# receiver.net
KiCad netlist of a schematic drawn in EAGLE
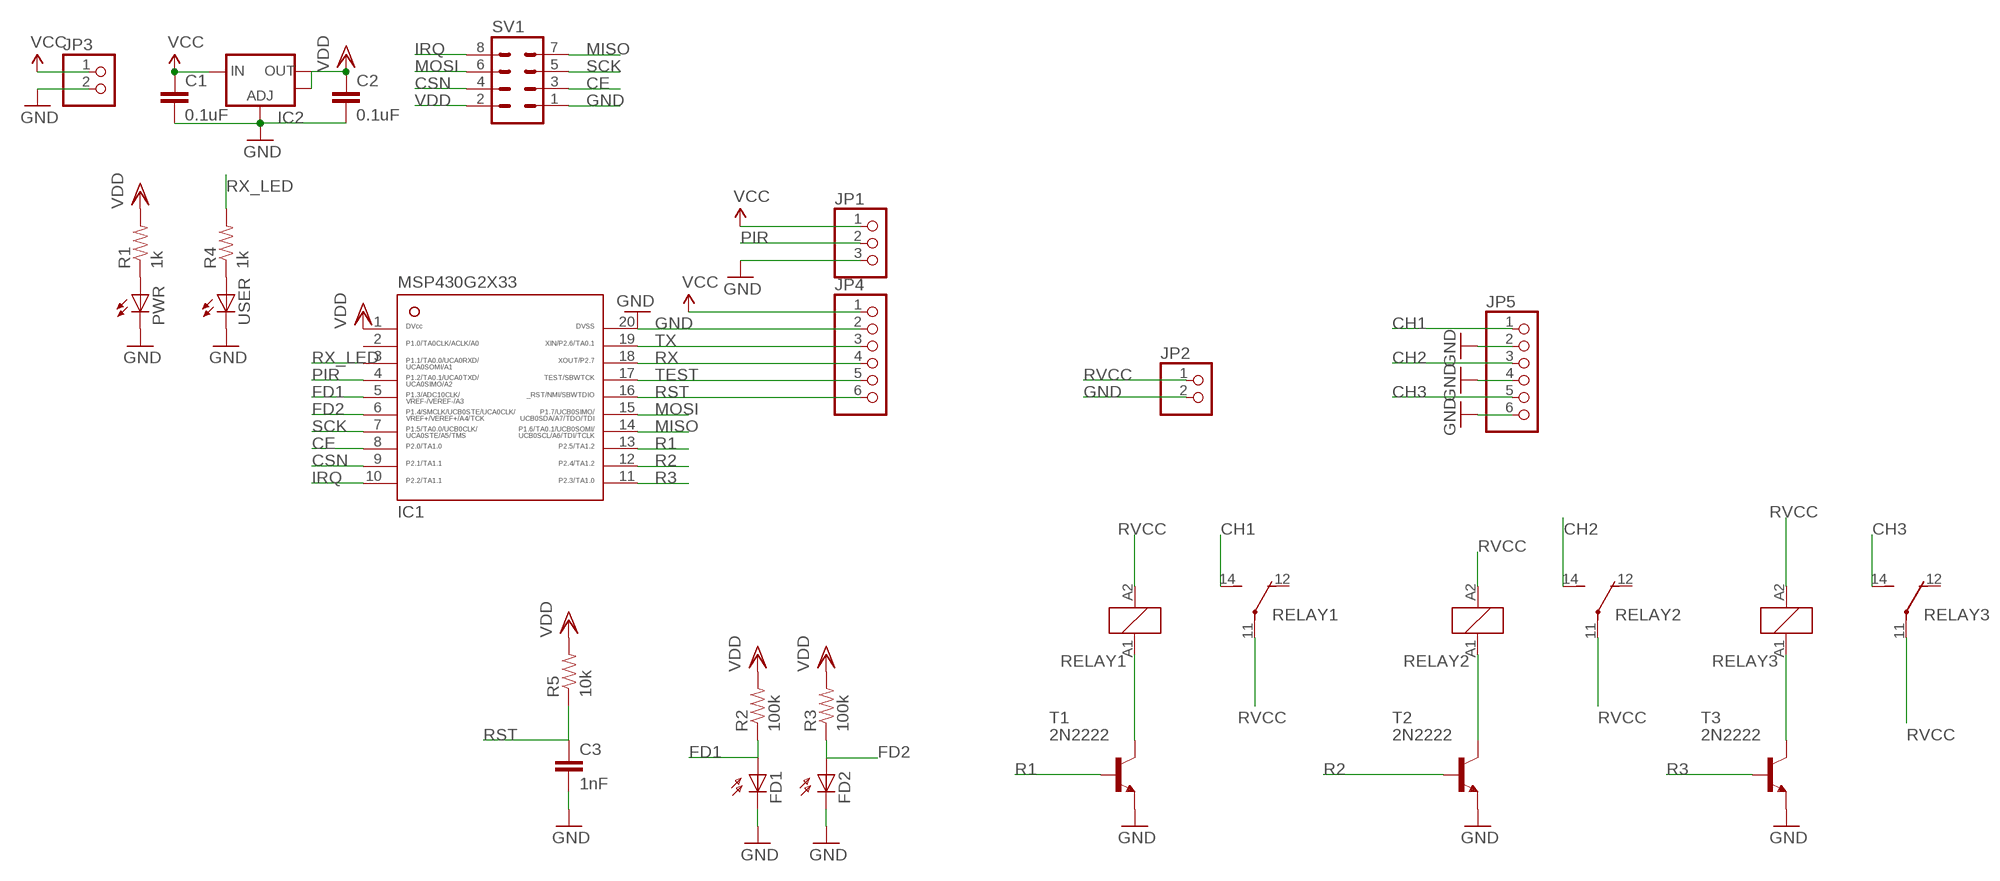
[diagram p0: schematic, sheet 1]

(export (version "E")
  (design (tool "Eeschema 10.0.6"))
  (components
    (comp (ref "C1")
      (value "0.1uF")
      (footprint "eagle-import:0603-CAP")
      (libsource (lib "eagle-import") (part "0.1UF-25V(+80/-20%)(0603)"))
    )
    (comp (ref "C2")
      (value "0.1uF")
      (footprint "eagle-import:0603-CAP")
      (libsource (lib "eagle-import") (part "0.1UF-25V(+80/-20%)(0603)"))
    )
    (comp (ref "C3")
      (value "1nF")
      (footprint "eagle-import:0603-CAP")
      (libsource (lib "eagle-import") (part "0.1UF-25V(+80/-20%)(0603)"))
    )
    (comp (ref "FD1")
      (value "BPX65")
      (footprint "eagle-import:BPX65")
      (fields (field (name "MPN") "BPX65."))
      (libsource (lib "eagle-import") (part "BPX65"))
    )
    (comp (ref "FD2")
      (value "BPX65")
      (footprint "eagle-import:BPX65")
      (fields (field (name "MPN") "BPX65."))
      (libsource (lib "eagle-import") (part "BPX65"))
    )
    (comp (ref "IC1")
      (value "MSP430G2X33-20PW20")
      (footprint "eagle-import:PW20")
      (libsource (lib "eagle-import") (part "MSP430G2X33-20PW20"))
    )
    (comp (ref "IC2")
      (value "V_REG_LM1117SOT223")
      (footprint "eagle-import:SOT223")
      (libsource (lib "eagle-import") (part "V_REG_LM1117SOT223"))
    )
    (comp (ref "JP1")
      (value "PINHD-1X3")
      (footprint "eagle-import:1X03")
      (libsource (lib "eagle-import") (part "PINHD-1X3"))
    )
    (comp (ref "JP2")
      (value "PINHD-1X2")
      (footprint "eagle-import:1X02")
      (libsource (lib "eagle-import") (part "PINHD-1X2"))
    )
    (comp (ref "JP3")
      (value "PINHD-1X2")
      (footprint "eagle-import:1X02")
      (libsource (lib "eagle-import") (part "PINHD-1X2"))
    )
    (comp (ref "JP4")
      (value "PINHD-1X6")
      (footprint "eagle-import:1X06")
      (libsource (lib "eagle-import") (part "PINHD-1X6"))
    )
    (comp (ref "JP5")
      (value "PINHD-1X6")
      (footprint "eagle-import:1X06")
      (libsource (lib "eagle-import") (part "PINHD-1X6"))
    )
    (comp (ref "PWR")
      (value "LEDCHIP-LED0805")
      (footprint "eagle-import:CHIP-LED0805")
      (libsource (lib "eagle-import") (part "LEDCHIP-LED0805"))
    )
    (comp (ref "R1")
      (value "1k")
      (footprint "eagle-import:0603")
      (libsource (lib "eagle-import") (part "0OHM1/10W5%(0603)"))
    )
    (comp (ref "R2")
      (value "100k")
      (footprint "eagle-import:0603")
      (libsource (lib "eagle-import") (part "0OHM1/10W5%(0603)"))
    )
    (comp (ref "R3")
      (value "100k")
      (footprint "eagle-import:0603")
      (libsource (lib "eagle-import") (part "0OHM1/10W5%(0603)"))
    )
    (comp (ref "R4")
      (value "1k")
      (footprint "eagle-import:0603")
      (libsource (lib "eagle-import") (part "0OHM1/10W5%(0603)"))
    )
    (comp (ref "R5")
      (value "10k")
      (footprint "eagle-import:0603")
      (libsource (lib "eagle-import") (part "0OHM1/10W5%(0603)"))
    )
    (comp (ref "RELAY1")
      (value "ZNS5106")
      (footprint "eagle-import:ZN5")
      (libsource (lib "eagle-import") (part "ZNS5106"))
    )
    (comp (ref "RELAY2")
      (value "ZNS5106")
      (footprint "eagle-import:ZN5")
      (libsource (lib "eagle-import") (part "ZNS5106"))
    )
    (comp (ref "RELAY3")
      (value "ZNS5106")
      (footprint "eagle-import:ZN5")
      (libsource (lib "eagle-import") (part "ZNS5106"))
    )
    (comp (ref "SV1")
      (value "MA04-2")
      (footprint "eagle-import:MA04-2")
      (libsource (lib "eagle-import") (part "MA04-2"))
    )
    (comp (ref "T1")
      (value "2N2222")
      (footprint "eagle-import:TO92-EBC-OVAL")
      (libsource (lib "eagle-import") (part "2N2222"))
    )
    (comp (ref "T2")
      (value "2N2222")
      (footprint "eagle-import:TO92-EBC-OVAL")
      (libsource (lib "eagle-import") (part "2N2222"))
    )
    (comp (ref "T3")
      (value "2N2222")
      (footprint "eagle-import:TO92-EBC-OVAL")
      (libsource (lib "eagle-import") (part "2N2222"))
    )
    (comp (ref "USER")
      (value "LEDCHIP-LED0805")
      (footprint "eagle-import:CHIP-LED0805")
      (libsource (lib "eagle-import") (part "LEDCHIP-LED0805"))
    )
  )
  (nets
    (net (code "1") (name "/CE") (class "Default")
      (node (ref "IC1") (pin "8") (pinfunction "8_8") (pintype "bidirectional"))
      (node (ref "SV1") (pin "3") (pinfunction "3_3") (pintype "passive"))
    )
    (net (code "2") (name "/CH1") (class "Default")
      (node (ref "JP5") (pin "1") (pinfunction "1_1") (pintype "passive"))
      (node (ref "RELAY1") (pin "14") (pinfunction "S_14") (pintype "passive"))
    )
    (net (code "3") (name "/CH2") (class "Default")
      (node (ref "JP5") (pin "3") (pinfunction "3_3") (pintype "passive"))
      (node (ref "RELAY2") (pin "14") (pinfunction "S_14") (pintype "passive"))
    )
    (net (code "4") (name "/CH3") (class "Default")
      (node (ref "JP5") (pin "5") (pinfunction "5_5") (pintype "passive"))
      (node (ref "RELAY3") (pin "14") (pinfunction "S_14") (pintype "passive"))
    )
    (net (code "5") (name "/CSN") (class "Default")
      (node (ref "IC1") (pin "9") (pinfunction "9_9") (pintype "bidirectional"))
      (node (ref "SV1") (pin "4") (pinfunction "4_4") (pintype "passive"))
    )
    (net (code "6") (name "/FD1") (class "Default")
      (node (ref "FD1") (pin "A") (pinfunction "A_A") (pintype "passive"))
      (node (ref "IC1") (pin "5") (pinfunction "5_5") (pintype "bidirectional"))
      (node (ref "R2") (pin "1") (pinfunction "1_1") (pintype "passive"))
    )
    (net (code "7") (name "/FD2") (class "Default")
      (node (ref "FD2") (pin "A") (pinfunction "A_A") (pintype "passive"))
      (node (ref "IC1") (pin "6") (pinfunction "6_6") (pintype "bidirectional"))
      (node (ref "R3") (pin "1") (pinfunction "1_1") (pintype "passive"))
    )
    (net (code "8") (name "/IRQ") (class "Default")
      (node (ref "IC1") (pin "10") (pinfunction "10_10") (pintype "bidirectional"))
      (node (ref "SV1") (pin "8") (pinfunction "8_8") (pintype "passive"))
    )
    (net (code "9") (name "/MISO") (class "Default")
      (node (ref "IC1") (pin "14") (pinfunction "14_14") (pintype "bidirectional"))
      (node (ref "SV1") (pin "7") (pinfunction "7_7") (pintype "passive"))
    )
    (net (code "10") (name "/MOSI") (class "Default")
      (node (ref "IC1") (pin "15") (pinfunction "15_15") (pintype "bidirectional"))
      (node (ref "SV1") (pin "6") (pinfunction "6_6") (pintype "passive"))
    )
    (net (code "11") (name "/PIR") (class "Default")
      (node (ref "IC1") (pin "4") (pinfunction "4_4") (pintype "bidirectional"))
      (node (ref "JP1") (pin "2") (pinfunction "2_2") (pintype "passive"))
    )
    (net (code "12") (name "/R1") (class "Default")
      (node (ref "IC1") (pin "13") (pinfunction "13_13") (pintype "bidirectional"))
      (node (ref "T1") (pin "B") (pinfunction "B_B") (pintype "passive"))
    )
    (net (code "13") (name "/R2") (class "Default")
      (node (ref "IC1") (pin "12") (pinfunction "12_12") (pintype "bidirectional"))
      (node (ref "T2") (pin "B") (pinfunction "B_B") (pintype "passive"))
    )
    (net (code "14") (name "/R3") (class "Default")
      (node (ref "IC1") (pin "11") (pinfunction "11_11") (pintype "bidirectional"))
      (node (ref "T3") (pin "B") (pinfunction "B_B") (pintype "passive"))
    )
    (net (code "15") (name "/RST") (class "Default")
      (node (ref "C3") (pin "1") (pinfunction "1_1") (pintype "passive"))
      (node (ref "IC1") (pin "16") (pinfunction "16_16") (pintype "bidirectional"))
      (node (ref "JP4") (pin "6") (pinfunction "6_6") (pintype "passive"))
      (node (ref "R5") (pin "1") (pinfunction "1_1") (pintype "passive"))
    )
    (net (code "16") (name "/RVCC") (class "Default")
      (node (ref "JP2") (pin "1") (pinfunction "1_1") (pintype "passive"))
      (node (ref "RELAY1") (pin "11") (pinfunction "P_11") (pintype "passive"))
      (node (ref "RELAY1") (pin "A2") (pinfunction "2_A2") (pintype "passive"))
      (node (ref "RELAY2") (pin "11") (pinfunction "P_11") (pintype "passive"))
      (node (ref "RELAY2") (pin "A2") (pinfunction "2_A2") (pintype "passive"))
      (node (ref "RELAY3") (pin "11") (pinfunction "P_11") (pintype "passive"))
      (node (ref "RELAY3") (pin "A2") (pinfunction "2_A2") (pintype "passive"))
    )
    (net (code "17") (name "/RX") (class "Default")
      (node (ref "IC1") (pin "18") (pinfunction "18_18") (pintype "bidirectional"))
      (node (ref "JP4") (pin "4") (pinfunction "4_4") (pintype "passive"))
    )
    (net (code "18") (name "/RX_LED") (class "Default")
      (node (ref "IC1") (pin "3") (pinfunction "3_3") (pintype "bidirectional"))
      (node (ref "R4") (pin "2") (pinfunction "2_2") (pintype "passive"))
    )
    (net (code "19") (name "/SCK") (class "Default")
      (node (ref "IC1") (pin "7") (pinfunction "7_7") (pintype "bidirectional"))
      (node (ref "SV1") (pin "5") (pinfunction "5_5") (pintype "passive"))
    )
    (net (code "20") (name "/TEST") (class "Default")
      (node (ref "IC1") (pin "17") (pinfunction "17_17") (pintype "bidirectional"))
      (node (ref "JP4") (pin "5") (pinfunction "5_5") (pintype "passive"))
    )
    (net (code "21") (name "/TX") (class "Default")
      (node (ref "IC1") (pin "19") (pinfunction "19_19") (pintype "bidirectional"))
      (node (ref "JP4") (pin "3") (pinfunction "3_3") (pintype "passive"))
    )
    (net (code "22") (name "GND") (class "Default")
      (node (ref "C1") (pin "2") (pinfunction "2_2") (pintype "passive"))
      (node (ref "C2") (pin "2") (pinfunction "2_2") (pintype "passive"))
      (node (ref "C3") (pin "2") (pinfunction "2_2") (pintype "passive"))
      (node (ref "FD1") (pin "K") (pinfunction "C_K") (pintype "passive"))
      (node (ref "FD2") (pin "K") (pinfunction "C_K") (pintype "passive"))
      (node (ref "IC1") (pin "20") (pinfunction "20_20") (pintype "bidirectional"))
      (node (ref "IC2") (pin "1") (pinfunction "ADJ_1") (pintype "input"))
      (node (ref "JP1") (pin "3") (pinfunction "3_3") (pintype "passive"))
      (node (ref "JP2") (pin "2") (pinfunction "2_2") (pintype "passive"))
      (node (ref "JP3") (pin "2") (pinfunction "2_2") (pintype "passive"))
      (node (ref "JP4") (pin "2") (pinfunction "2_2") (pintype "passive"))
      (node (ref "JP5") (pin "2") (pinfunction "2_2") (pintype "passive"))
      (node (ref "JP5") (pin "4") (pinfunction "4_4") (pintype "passive"))
      (node (ref "JP5") (pin "6") (pinfunction "6_6") (pintype "passive"))
      (node (ref "PWR") (pin "C") (pinfunction "C_C") (pintype "passive"))
      (node (ref "SV1") (pin "1") (pinfunction "1_1") (pintype "passive"))
      (node (ref "T1") (pin "E") (pinfunction "E_E") (pintype "passive"))
      (node (ref "T2") (pin "E") (pinfunction "E_E") (pintype "passive"))
      (node (ref "T3") (pin "E") (pinfunction "E_E") (pintype "passive"))
      (node (ref "USER") (pin "C") (pinfunction "C_C") (pintype "passive"))
    )
    (net (code "23") (name "Net-(PWR-PadA)") (class "Default")
      (node (ref "PWR") (pin "A") (pinfunction "A_A") (pintype "passive"))
      (node (ref "R1") (pin "1") (pinfunction "1_1") (pintype "passive"))
    )
    (net (code "24") (name "Net-(R4-Pad1)") (class "Default")
      (node (ref "R4") (pin "1") (pinfunction "1_1") (pintype "passive"))
      (node (ref "USER") (pin "A") (pinfunction "A_A") (pintype "passive"))
    )
    (net (code "25") (name "Net-(RELAY1A-1)") (class "Default")
      (node (ref "RELAY1") (pin "A1") (pinfunction "1_A1") (pintype "passive"))
      (node (ref "T1") (pin "C") (pinfunction "C_C") (pintype "passive"))
    )
    (net (code "26") (name "Net-(RELAY2A-1)") (class "Default")
      (node (ref "RELAY2") (pin "A1") (pinfunction "1_A1") (pintype "passive"))
      (node (ref "T2") (pin "C") (pinfunction "C_C") (pintype "passive"))
    )
    (net (code "27") (name "Net-(RELAY3A-1)") (class "Default")
      (node (ref "RELAY3") (pin "A1") (pinfunction "1_A1") (pintype "passive"))
      (node (ref "T3") (pin "C") (pinfunction "C_C") (pintype "passive"))
    )
    (net (code "28") (name "VCC") (class "Default")
      (node (ref "C1") (pin "1") (pinfunction "1_1") (pintype "passive"))
      (node (ref "IC2") (pin "3") (pinfunction "IN_3") (pintype "input"))
      (node (ref "JP1") (pin "1") (pinfunction "1_1") (pintype "passive"))
      (node (ref "JP3") (pin "1") (pinfunction "1_1") (pintype "passive"))
      (node (ref "JP4") (pin "1") (pinfunction "1_1") (pintype "passive"))
    )
    (net (code "29") (name "VDD") (class "Default")
      (node (ref "C2") (pin "1") (pinfunction "1_1") (pintype "passive"))
      (node (ref "IC1") (pin "1") (pinfunction "1_1") (pintype "bidirectional"))
      (node (ref "IC2") (pin "2") (pinfunction "OUT_2") (pintype "output"))
      (node (ref "IC2") (pin "4") (pinfunction "OUT_4") (pintype "output"))
      (node (ref "R1") (pin "2") (pinfunction "2_2") (pintype "passive"))
      (node (ref "R2") (pin "2") (pinfunction "2_2") (pintype "passive"))
      (node (ref "R3") (pin "2") (pinfunction "2_2") (pintype "passive"))
      (node (ref "R5") (pin "2") (pinfunction "2_2") (pintype "passive"))
      (node (ref "SV1") (pin "2") (pinfunction "2_2") (pintype "passive"))
    )
    (net (code "30") (name "unconnected-(IC1-Pad2)") (class "Default")
      (node (ref "IC1") (pin "2") (pinfunction "2_2") (pintype "bidirectional"))
    )
    (net (code "31") (name "unconnected-(RELAY1B-O-Pad12)") (class "Default")
      (node (ref "RELAY1") (pin "12") (pinfunction "O_12") (pintype "passive"))
    )
    (net (code "32") (name "unconnected-(RELAY2B-O-Pad12)") (class "Default")
      (node (ref "RELAY2") (pin "12") (pinfunction "O_12") (pintype "passive"))
    )
    (net (code "33") (name "unconnected-(RELAY3B-O-Pad12)") (class "Default")
      (node (ref "RELAY3") (pin "12") (pinfunction "O_12") (pintype "passive"))
    )
  )
)
